# ProProject_NANO.net
KiCad netlist of a schematic drawn in EasyEDA Pro
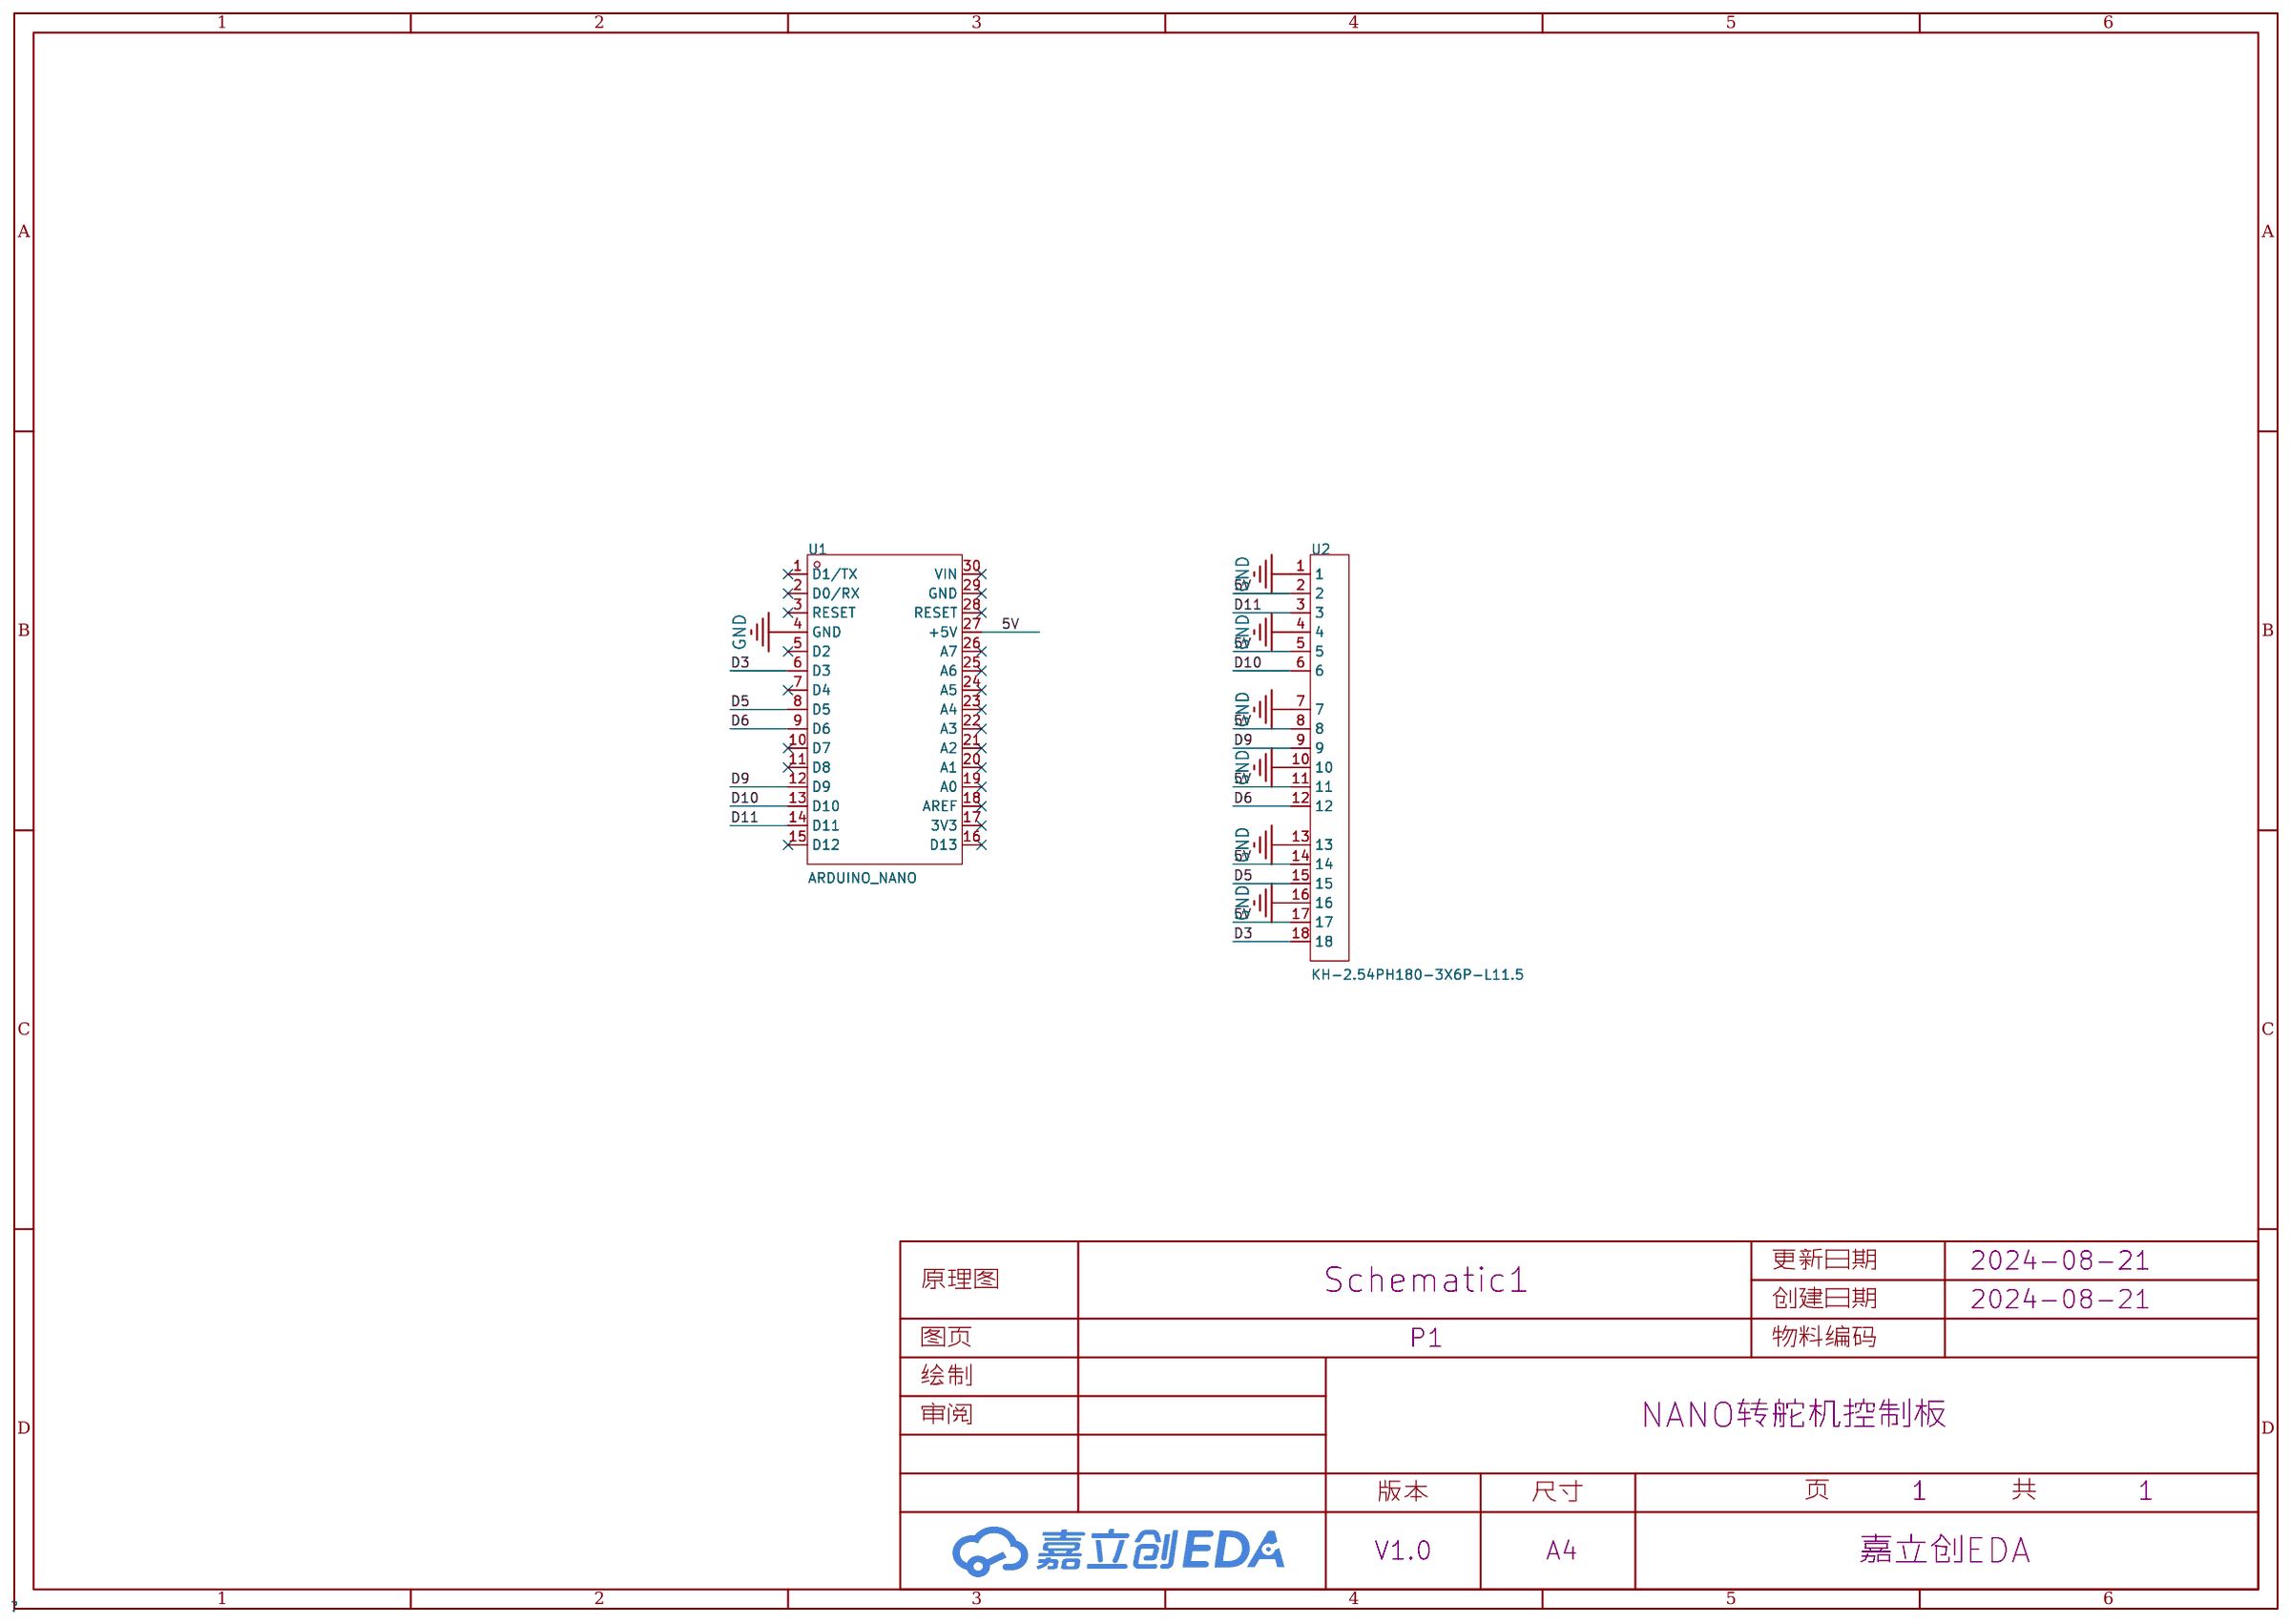
[diagram p0: schematic sheet]

(export (version "E")
  (design (tool "Eeschema 10.0.6"))
  (components
    (comp (ref "U1")
      (value "ARDUINO_NANO")
      (footprint "easyedapro:COMM-TH_ARDUINO_NANO")
      (libsource (lib "easyedapro") (part "ARDUINO_NANO"))
    )
    (comp (ref "U2")
      (value "KH-2.54PH180-3X6P-L11.5")
      (footprint "easyedapro:HDR-TH_18P-P2.54-V-M-R3-C6-S5.08")
      (description "插针结构:3x6P;间距:2.54mm;排数:三排;")
      (fields (field (name "Manufacturer") "kinghelm(金航标)"))
      (libsource (lib "easyedapro") (part "KH-2.54PH180-3X6P-L11.5"))
    )
  )
  (nets
    (net (code "1") (name "/5V") (class "Default")
      (node (ref "U1") (pin "27") (pinfunction "+5V_27") (pintype "unspecified"))
      (node (ref "U2") (pin "11") (pinfunction "11_11") (pintype "unspecified"))
      (node (ref "U2") (pin "14") (pinfunction "14_14") (pintype "unspecified"))
      (node (ref "U2") (pin "17") (pinfunction "17_17") (pintype "unspecified"))
      (node (ref "U2") (pin "2") (pinfunction "2_2") (pintype "unspecified"))
      (node (ref "U2") (pin "5") (pinfunction "5_5") (pintype "unspecified"))
      (node (ref "U2") (pin "8") (pinfunction "8_8") (pintype "unspecified"))
    )
    (net (code "2") (name "/D3") (class "Default")
      (node (ref "U1") (pin "6") (pinfunction "D3_6") (pintype "unspecified"))
      (node (ref "U2") (pin "18") (pinfunction "18_18") (pintype "unspecified"))
    )
    (net (code "3") (name "/D5") (class "Default")
      (node (ref "U1") (pin "8") (pinfunction "D5_8") (pintype "unspecified"))
      (node (ref "U2") (pin "15") (pinfunction "15_15") (pintype "unspecified"))
    )
    (net (code "4") (name "/D6") (class "Default")
      (node (ref "U1") (pin "9") (pinfunction "D6_9") (pintype "unspecified"))
      (node (ref "U2") (pin "12") (pinfunction "12_12") (pintype "unspecified"))
    )
    (net (code "5") (name "/D9") (class "Default")
      (node (ref "U1") (pin "12") (pinfunction "D9_12") (pintype "unspecified"))
      (node (ref "U2") (pin "9") (pinfunction "9_9") (pintype "unspecified"))
    )
    (net (code "6") (name "/D10") (class "Default")
      (node (ref "U1") (pin "13") (pinfunction "D10_13") (pintype "unspecified"))
      (node (ref "U2") (pin "6") (pinfunction "6_6") (pintype "unspecified"))
    )
    (net (code "7") (name "/D11") (class "Default")
      (node (ref "U1") (pin "14") (pinfunction "D11_14") (pintype "unspecified"))
      (node (ref "U2") (pin "3") (pinfunction "3_3") (pintype "unspecified"))
    )
    (net (code "8") (name "GND") (class "Default")
      (node (ref "U1") (pin "4") (pinfunction "GND_4") (pintype "unspecified"))
      (node (ref "U2") (pin "1") (pinfunction "1_1") (pintype "unspecified"))
      (node (ref "U2") (pin "10") (pinfunction "10_10") (pintype "unspecified"))
      (node (ref "U2") (pin "13") (pinfunction "13_13") (pintype "unspecified"))
      (node (ref "U2") (pin "16") (pinfunction "16_16") (pintype "unspecified"))
      (node (ref "U2") (pin "4") (pinfunction "4_4") (pintype "unspecified"))
      (node (ref "U2") (pin "7") (pinfunction "7_7") (pintype "unspecified"))
    )
    (net (code "9") (name "unconnected-(U1-3V3-Pad17)") (class "Default")
      (node (ref "U1") (pin "17") (pinfunction "3V3_17") (pintype "unspecified+no_connect"))
    )
    (net (code "10") (name "unconnected-(U1-A0-Pad19)") (class "Default")
      (node (ref "U1") (pin "19") (pinfunction "A0_19") (pintype "unspecified+no_connect"))
    )
    (net (code "11") (name "unconnected-(U1-A1-Pad20)") (class "Default")
      (node (ref "U1") (pin "20") (pinfunction "A1_20") (pintype "unspecified+no_connect"))
    )
    (net (code "12") (name "unconnected-(U1-A2-Pad21)") (class "Default")
      (node (ref "U1") (pin "21") (pinfunction "A2_21") (pintype "unspecified+no_connect"))
    )
    (net (code "13") (name "unconnected-(U1-A3-Pad22)") (class "Default")
      (node (ref "U1") (pin "22") (pinfunction "A3_22") (pintype "unspecified+no_connect"))
    )
    (net (code "14") (name "unconnected-(U1-A4-Pad23)") (class "Default")
      (node (ref "U1") (pin "23") (pinfunction "A4_23") (pintype "unspecified+no_connect"))
    )
    (net (code "15") (name "unconnected-(U1-A5-Pad24)") (class "Default")
      (node (ref "U1") (pin "24") (pinfunction "A5_24") (pintype "unspecified+no_connect"))
    )
    (net (code "16") (name "unconnected-(U1-A6-Pad25)") (class "Default")
      (node (ref "U1") (pin "25") (pinfunction "A6_25") (pintype "unspecified+no_connect"))
    )
    (net (code "17") (name "unconnected-(U1-A7-Pad26)") (class "Default")
      (node (ref "U1") (pin "26") (pinfunction "A7_26") (pintype "unspecified+no_connect"))
    )
    (net (code "18") (name "unconnected-(U1-AREF-Pad18)") (class "Default")
      (node (ref "U1") (pin "18") (pinfunction "AREF_18") (pintype "unspecified+no_connect"))
    )
    (net (code "19") (name "unconnected-(U1-D0{slash}RX-Pad2)") (class "Default")
      (node (ref "U1") (pin "2") (pinfunction "D0/RX_2") (pintype "unspecified+no_connect"))
    )
    (net (code "20") (name "unconnected-(U1-D1{slash}TX-Pad1)") (class "Default")
      (node (ref "U1") (pin "1") (pinfunction "D1/TX_1") (pintype "unspecified+no_connect"))
    )
    (net (code "21") (name "unconnected-(U1-D2-Pad5)") (class "Default")
      (node (ref "U1") (pin "5") (pinfunction "D2_5") (pintype "unspecified+no_connect"))
    )
    (net (code "22") (name "unconnected-(U1-D4-Pad7)") (class "Default")
      (node (ref "U1") (pin "7") (pinfunction "D4_7") (pintype "unspecified+no_connect"))
    )
    (net (code "23") (name "unconnected-(U1-D7-Pad10)") (class "Default")
      (node (ref "U1") (pin "10") (pinfunction "D7_10") (pintype "unspecified+no_connect"))
    )
    (net (code "24") (name "unconnected-(U1-D8-Pad11)") (class "Default")
      (node (ref "U1") (pin "11") (pinfunction "D8_11") (pintype "unspecified+no_connect"))
    )
    (net (code "25") (name "unconnected-(U1-D12-Pad15)") (class "Default")
      (node (ref "U1") (pin "15") (pinfunction "D12_15") (pintype "unspecified+no_connect"))
    )
    (net (code "26") (name "unconnected-(U1-D13-Pad16)") (class "Default")
      (node (ref "U1") (pin "16") (pinfunction "D13_16") (pintype "unspecified+no_connect"))
    )
    (net (code "27") (name "unconnected-(U1-GND-Pad29)") (class "Default")
      (node (ref "U1") (pin "29") (pinfunction "GND_29") (pintype "unspecified+no_connect"))
    )
    (net (code "28") (name "unconnected-(U1-RESET-Pad3)") (class "Default")
      (node (ref "U1") (pin "3") (pinfunction "RESET_3") (pintype "unspecified+no_connect"))
    )
    (net (code "29") (name "unconnected-(U1-RESET-Pad28)") (class "Default")
      (node (ref "U1") (pin "28") (pinfunction "RESET_28") (pintype "unspecified+no_connect"))
    )
    (net (code "30") (name "unconnected-(U1-VIN-Pad30)") (class "Default")
      (node (ref "U1") (pin "30") (pinfunction "VIN_30") (pintype "unspecified+no_connect"))
    )
  )
)
